# Keypadmacro.net
KiCad netlist of a schematic drawn in Altium Designer
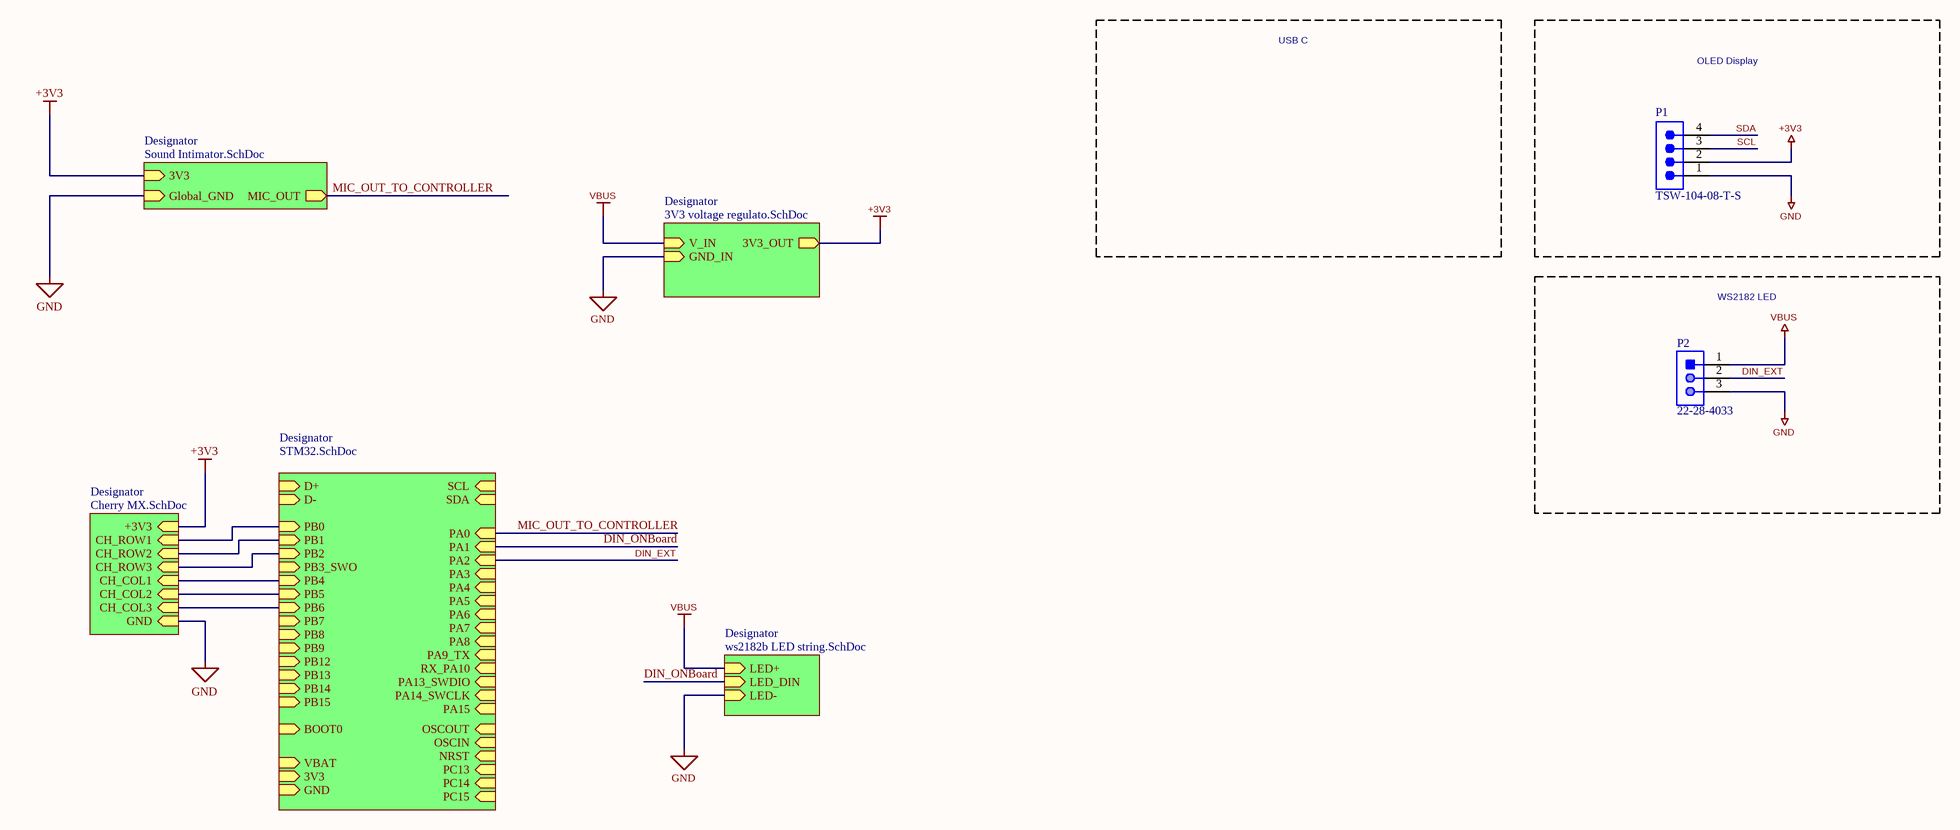
[diagram p0: Keypadmacro.SchDoc]

(export (version "E")
  (design (tool "Eeschema 10.0.6"))
  (components
    (comp (ref "P1")
      (value "TSW-104-08-T-S")
      (footprint "SMTC-TSW-104-08-X-S")
      (description "0.025\" SQ Post Header, Through-hole, Vertical, -55 to 105 degC, 2.54 mm Pitch, 4-Pin, Male, RoHS")
      (fields (field (name "MANUFACTURER") "Samtec"))
      (libsource (lib "Altium Content Vault") (part "SMTC-TSW-104-08-X-S"))
    )
    (comp (ref "P2")
      (value "22-28-4033")
      (footprint "MOLX-22-28-4033_V")
      (description "Male Header, Pitch 2.54 mm, 1 x 3 Position, Height 8.38 mm, Tail Length 3.18 mm, RoHS, Bulk")
      (fields (field (name "MANUFACTURER") "Molex"))
      (libsource (lib "Altium Content Vault") (part "CN-1P-M-R3"))
    )
  )
  (nets
    (net (code "1") (name "+3V3") (class "Default")
      (node (ref "P1") (pin "2") (pinfunction "2_2") (pintype "passive"))
    )
    (net (code "12") (name "/DIN_EXT") (class "Default")
      (node (ref "P2") (pin "2") (pinfunction "2_2") (pintype "passive"))
    )
    (net (code "41") (name "/SCL") (class "Default")
      (node (ref "P1") (pin "3") (pinfunction "3_3") (pintype "passive"))
    )
    (net (code "43") (name "/SDA") (class "Default")
      (node (ref "P1") (pin "4") (pinfunction "4_4") (pintype "passive"))
    )
    (net (code "46") (name "GND") (class "Default")
      (node (ref "P1") (pin "1") (pinfunction "1_1") (pintype "passive"))
      (node (ref "P2") (pin "3") (pinfunction "3_3") (pintype "passive"))
    )
    (net (code "47") (name "VBUS") (class "Default")
      (node (ref "P2") (pin "1") (pinfunction "1_1") (pintype "passive"))
    )
  )
)
